# RiskChemi_Sensors_V2_04.net
KiCad netlist of a schematic drawn in Altium Designer
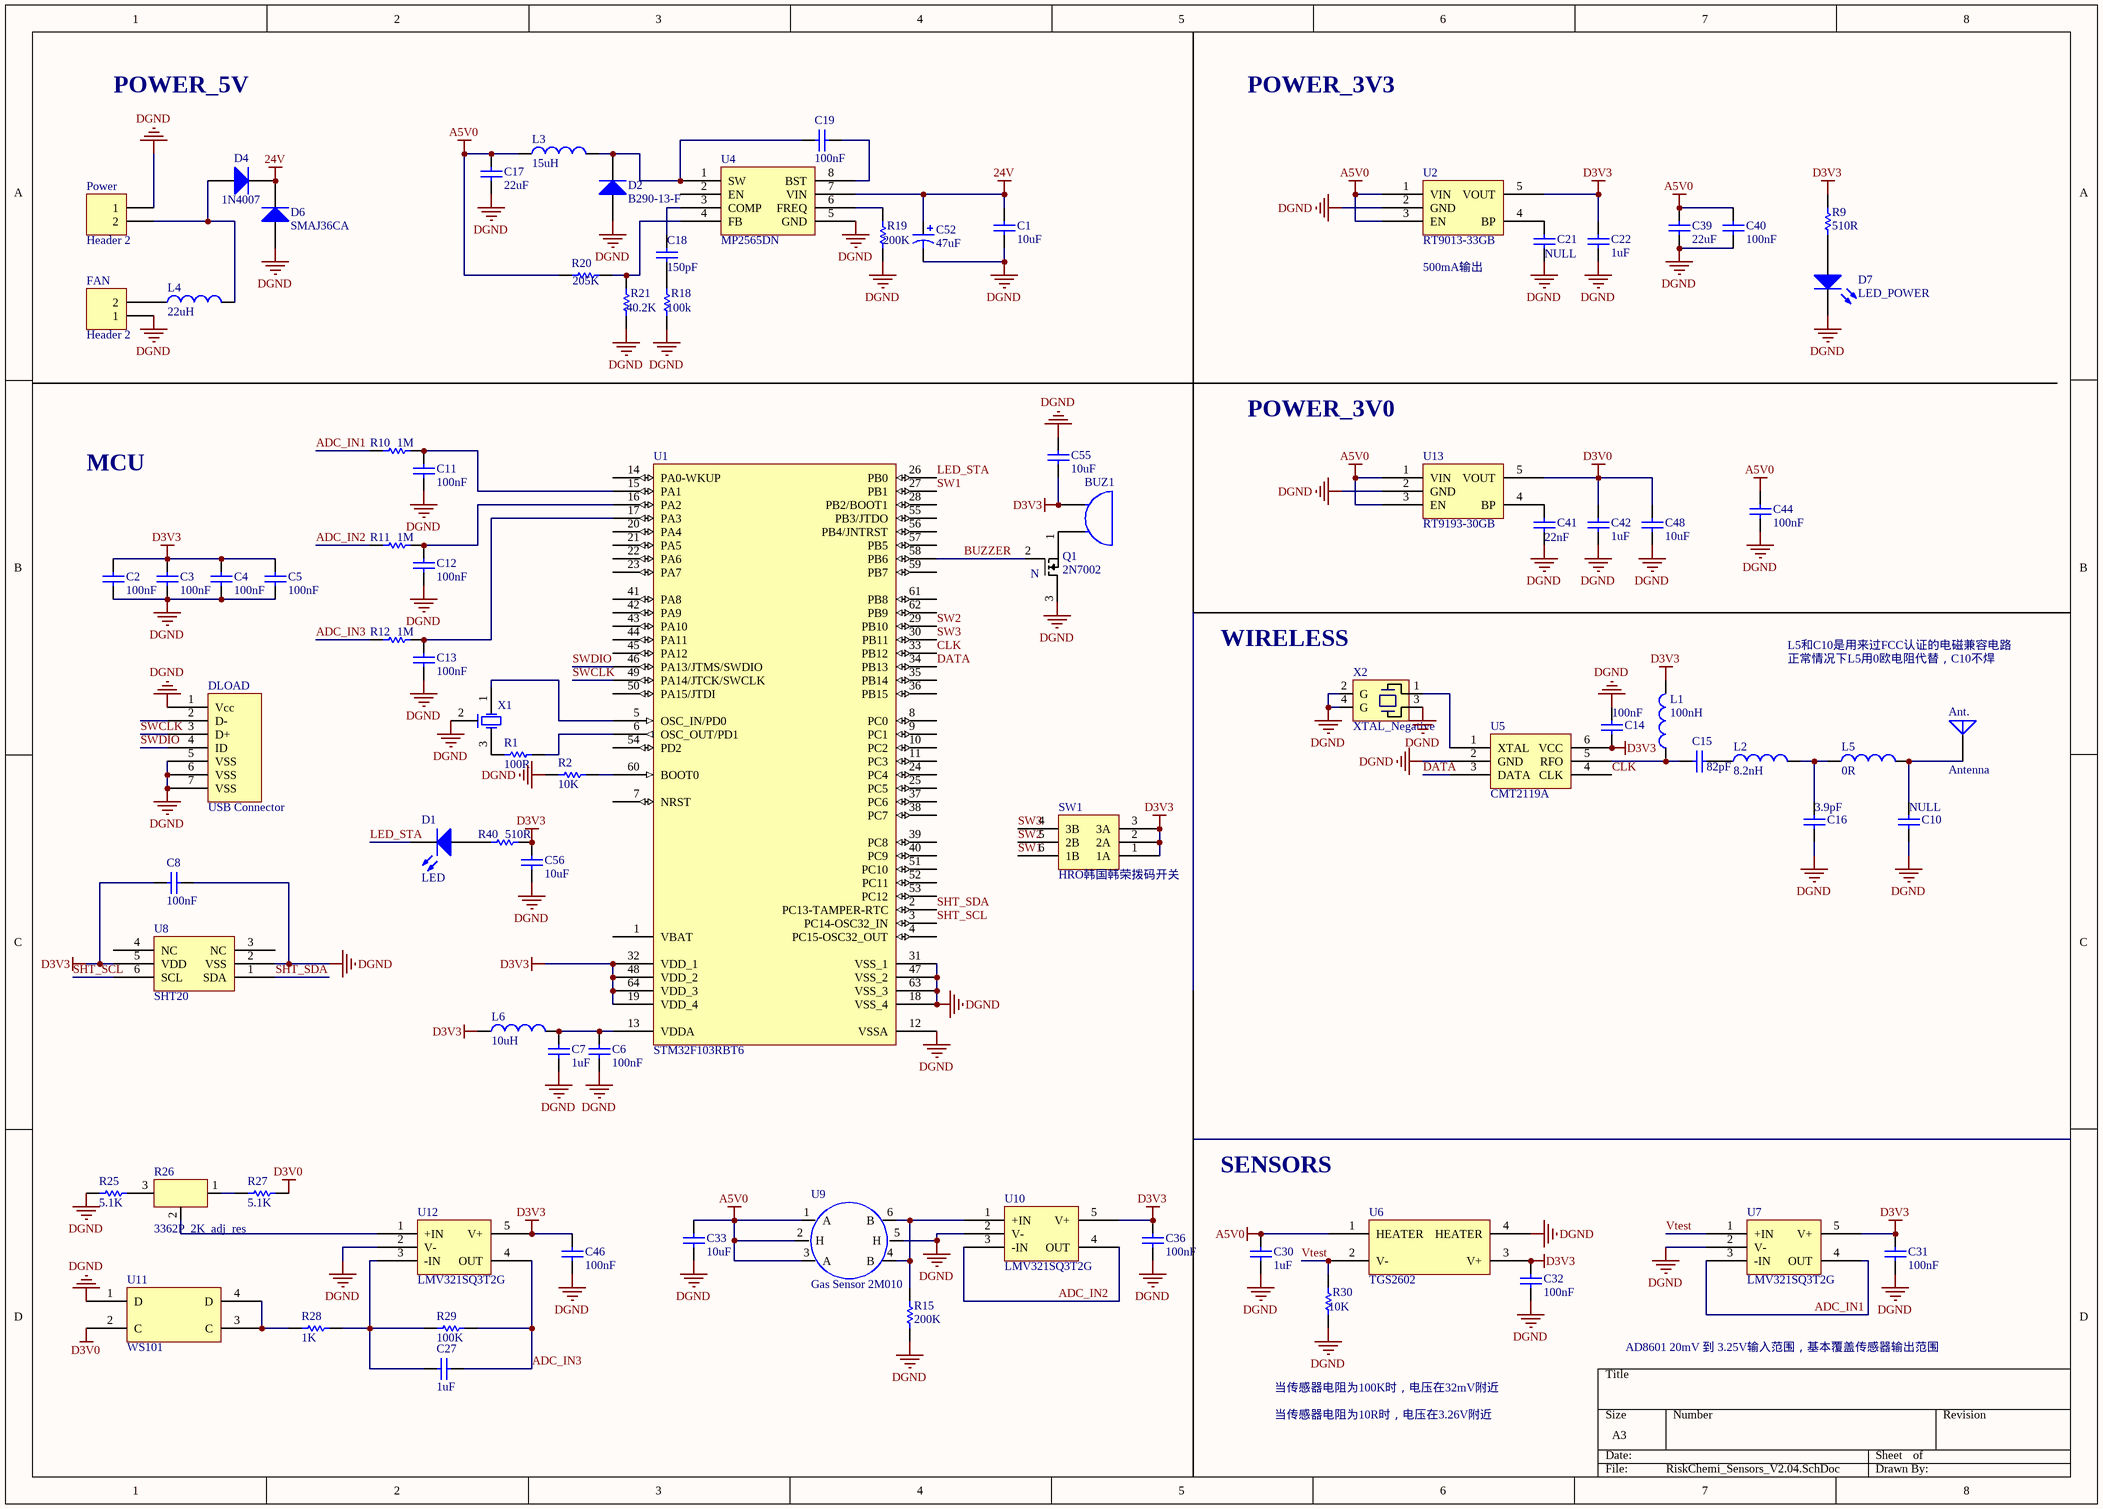
[diagram p0: RiskChemi_Sensors_V2.04.SchDoc]

(export (version "E")
  (design (tool "Eeschema 10.0.6"))
  (components
    (comp (ref "Ant.")
      (value "Antenna")
      (footprint "PIN1")
      (description "Generic Antenna")
      (fields (field (name "PUBLISHER") "Altium Limited"))
      (libsource (lib "Miscellaneous Devices") (part "Antenna"))
    )
    (comp (ref "BUZ1")
      (value "BUZZER 0905 through hole")
      (footprint "BUZ0905")
      (description "Buzzer")
      (libsource (lib "杂元件库") (part "BUZZER"))
    )
    (comp (ref "C1")
      (value "10uF")
      (footprint "0805")
      (description "Capacitor,50V")
      (fields (field (name "PUBLISHER") "Altium Limited"))
      (libsource (lib "Miscellaneous Devices") (part "Cap"))
    )
    (comp (ref "C2")
      (value "100nF")
      (footprint "BinFeng:0603")
      (description "Capacitor")
      (fields (field (name "PUBLISHER") "Altium Limited"))
      (libsource (lib "Miscellaneous Devices") (part "Cap"))
    )
    (comp (ref "C3")
      (value "100nF")
      (footprint "BinFeng:0603")
      (description "Capacitor")
      (fields (field (name "PUBLISHER") "Altium Limited"))
      (libsource (lib "Miscellaneous Devices") (part "Cap"))
    )
    (comp (ref "C4")
      (value "100nF")
      (footprint "BinFeng:0603")
      (description "Capacitor")
      (fields (field (name "PUBLISHER") "Altium Limited"))
      (libsource (lib "Miscellaneous Devices") (part "Cap"))
    )
    (comp (ref "C5")
      (value "100nF")
      (footprint "BinFeng:0603")
      (description "Capacitor")
      (fields (field (name "PUBLISHER") "Altium Limited"))
      (libsource (lib "Miscellaneous Devices") (part "Cap"))
    )
    (comp (ref "C6")
      (value "100nF")
      (footprint "BinFeng:0603")
      (description "Capacitor")
      (fields (field (name "PUBLISHER") "Altium Limited"))
      (libsource (lib "Miscellaneous Devices") (part "Cap"))
    )
    (comp (ref "C7")
      (value "1uF")
      (footprint "BinFeng:0603")
      (description "Capacitor")
      (fields (field (name "PUBLISHER") "Altium Limited"))
      (libsource (lib "Miscellaneous Devices") (part "Cap"))
    )
    (comp (ref "C8")
      (value "100nF")
      (footprint "BinFeng:0603")
      (description "Capacitor")
      (fields (field (name "PUBLISHER") "Altium Limited"))
      (libsource (lib "Miscellaneous Devices") (part "Cap"))
    )
    (comp (ref "C10")
      (value "NULL")
      (footprint "BinFeng:0402")
      (description "Capacitor")
      (fields (field (name "PUBLISHER") "Altium Limited"))
      (libsource (lib "Miscellaneous Devices") (part "Cap"))
    )
    (comp (ref "C11")
      (value "100nF")
      (footprint "BinFeng:0603")
      (description "Capacitor")
      (fields (field (name "PUBLISHER") "Altium Limited"))
      (libsource (lib "Miscellaneous Devices") (part "Cap"))
    )
    (comp (ref "C12")
      (value "100nF")
      (footprint "BinFeng:0603")
      (description "Capacitor")
      (fields (field (name "PUBLISHER") "Altium Limited"))
      (libsource (lib "Miscellaneous Devices") (part "Cap"))
    )
    (comp (ref "C13")
      (value "100nF")
      (footprint "BinFeng:0603")
      (description "Capacitor")
      (fields (field (name "PUBLISHER") "Altium Limited"))
      (libsource (lib "Miscellaneous Devices") (part "Cap"))
    )
    (comp (ref "C14")
      (value "100nF")
      (footprint "BinFeng:0402")
      (description "Capacitor")
      (fields (field (name "PUBLISHER") "Altium Limited"))
      (libsource (lib "Miscellaneous Devices") (part "Cap"))
    )
    (comp (ref "C15")
      (value "82pF")
      (footprint "BinFeng:0402")
      (description "Capacitor")
      (fields (field (name "PUBLISHER") "Altium Limited"))
      (libsource (lib "Miscellaneous Devices") (part "Cap"))
    )
    (comp (ref "C16")
      (value "3.9pF")
      (footprint "BinFeng:0402")
      (description "Capacitor")
      (fields (field (name "PUBLISHER") "Altium Limited"))
      (libsource (lib "Miscellaneous Devices") (part "Cap"))
    )
    (comp (ref "C17")
      (value "22uF")
      (footprint "0805")
      (description "Capacitor,50V")
      (fields (field (name "PUBLISHER") "Altium Limited"))
      (libsource (lib "Miscellaneous Devices") (part "Cap"))
    )
    (comp (ref "C18")
      (value "150pF")
      (footprint "BinFeng:0603")
      (description "Capacitor")
      (fields (field (name "PUBLISHER") "Altium Limited"))
      (libsource (lib "Miscellaneous Devices") (part "Cap"))
    )
    (comp (ref "C19")
      (value "100nF")
      (footprint "BinFeng:0603")
      (description "Capacitor")
      (fields (field (name "PUBLISHER") "Altium Limited"))
      (libsource (lib "Miscellaneous Devices") (part "Cap"))
    )
    (comp (ref "C21")
      (value "NULL")
      (footprint "BinFeng:0402")
      (description "Capacitor")
      (fields (field (name "PUBLISHER") "Altium Limited"))
      (libsource (lib "Miscellaneous Devices") (part "Cap"))
    )
    (comp (ref "C22")
      (value "1uF")
      (footprint "BinFeng:0402")
      (description "Capacitor")
      (fields (field (name "PUBLISHER") "Altium Limited"))
      (libsource (lib "Miscellaneous Devices") (part "Cap"))
    )
    (comp (ref "C27")
      (value "1uF")
      (footprint "BinFeng:0603")
      (description "Capacitor")
      (fields (field (name "PUBLISHER") "Altium Limited"))
      (libsource (lib "Miscellaneous Devices") (part "Cap"))
    )
    (comp (ref "C30")
      (value "1uF")
      (footprint "BinFeng:0603")
      (description "Capacitor")
      (fields (field (name "PUBLISHER") "Altium Limited"))
      (libsource (lib "Miscellaneous Devices") (part "Cap"))
    )
    (comp (ref "C31")
      (value "100nF")
      (footprint "BinFeng:0603")
      (description "Capacitor")
      (fields (field (name "PUBLISHER") "Altium Limited"))
      (libsource (lib "Miscellaneous Devices") (part "Cap"))
    )
    (comp (ref "C32")
      (value "100nF")
      (footprint "BinFeng:0603")
      (description "Capacitor")
      (fields (field (name "PUBLISHER") "Altium Limited"))
      (libsource (lib "Miscellaneous Devices") (part "Cap"))
    )
    (comp (ref "C33")
      (value "10uF")
      (footprint "0805")
      (description "Capacitor")
      (fields (field (name "PUBLISHER") "Altium Limited"))
      (libsource (lib "Miscellaneous Devices") (part "Cap"))
    )
    (comp (ref "C36")
      (value "100nF")
      (footprint "BinFeng:0603")
      (description "Capacitor")
      (fields (field (name "PUBLISHER") "Altium Limited"))
      (libsource (lib "Miscellaneous Devices") (part "Cap"))
    )
    (comp (ref "C39")
      (value "22uF")
      (footprint "1206")
      (description "Capacitor")
      (fields (field (name "PUBLISHER") "Altium Limited"))
      (libsource (lib "Miscellaneous Devices") (part "Cap"))
    )
    (comp (ref "C40")
      (value "100nF")
      (footprint "BinFeng:0402")
      (description "Capacitor")
      (fields (field (name "PUBLISHER") "Altium Limited"))
      (libsource (lib "Miscellaneous Devices") (part "Cap"))
    )
    (comp (ref "C41")
      (value "22nF")
      (footprint "BinFeng:0402")
      (description "Capacitor")
      (fields (field (name "PUBLISHER") "Altium Limited"))
      (libsource (lib "Miscellaneous Devices") (part "Cap"))
    )
    (comp (ref "C42")
      (value "1uF")
      (footprint "BinFeng:0402")
      (description "Capacitor")
      (fields (field (name "PUBLISHER") "Altium Limited"))
      (libsource (lib "Miscellaneous Devices") (part "Cap"))
    )
    (comp (ref "C44")
      (value "100nF")
      (footprint "BinFeng:0402")
      (description "Capacitor")
      (fields (field (name "PUBLISHER") "Altium Limited"))
      (libsource (lib "Miscellaneous Devices") (part "Cap"))
    )
    (comp (ref "C46")
      (value "100nF")
      (footprint "BinFeng:0603")
      (description "Capacitor")
      (fields (field (name "PUBLISHER") "Altium Limited"))
      (libsource (lib "Miscellaneous Devices") (part "Cap"))
    )
    (comp (ref "C48")
      (value "10uF")
      (footprint "0805")
      (description "Capacitor")
      (fields (field (name "PUBLISHER") "Altium Limited"))
      (libsource (lib "Miscellaneous Devices") (part "Cap"))
    )
    (comp (ref "C52")
      (value "47uF")
      (footprint "cap_pol_8*10.2")
      (description "Polarized Capacitor (Radial)")
      (fields (field (name "PUBLISHER") "Altium Limited"))
      (libsource (lib "Miscellaneous Devices") (part "Cap Pol1"))
    )
    (comp (ref "C55")
      (value "10uF")
      (footprint "0805")
      (description "Capacitor")
      (fields (field (name "PUBLISHER") "Altium Limited"))
      (libsource (lib "Miscellaneous Devices") (part "Cap"))
    )
    (comp (ref "C56")
      (value "10uF")
      (footprint "0805")
      (description "Capacitor")
      (fields (field (name "PUBLISHER") "Altium Limited"))
      (libsource (lib "Miscellaneous Devices") (part "Cap"))
    )
    (comp (ref "D1")
      (value "LED")
      (footprint "1206_LED")
      (description "Typical INFRARED GaAs LED")
      (fields (field (name "PUBLISHER") "Altium Limited"))
      (libsource (lib "Miscellaneous Devices") (part "LED0"))
    )
    (comp (ref "D2")
      (value "B290-13-F")
      (footprint "B290")
      (description "Default Diode")
      (fields (field (name "PUBLISHER") "Altium Limited"))
      (libsource (lib "Miscellaneous Devices") (part "Diode"))
    )
    (comp (ref "D4")
      (value "1N4007")
      (footprint "6032_pol")
      (description "1 Amp General Purpose Rectifier")
      (fields (field (name "PUBLISHER") "Altium Limited"))
      (libsource (lib "Miscellaneous Devices") (part "Diode 1N4007"))
    )
    (comp (ref "D6")
      (value "SMAJ36CA")
      (footprint "B290")
      (description "1 Amp General Purpose Rectifier")
      (fields (field (name "PUBLISHER") "Altium Limited"))
      (libsource (lib "Miscellaneous Devices") (part "Diode 1N4007"))
    )
    (comp (ref "D7")
      (value "LED_POWER")
      (footprint "1206_LED")
      (description "Typical INFRARED GaAs LED")
      (fields (field (name "PUBLISHER") "Altium Limited"))
      (libsource (lib "Miscellaneous Devices") (part "LED0"))
    )
    (comp (ref "DLOAD")
      (value "USB Connector")
      (footprint "Mini_USB")
      (libsource (lib "BinFeng_Connectors") (part "Component_1"))
    )
    (comp (ref "FAN")
      (value "Header 2")
      (footprint "HDR1X2")
      (description "Header, 2-Pin")
      (fields (field (name "PUBLISHER") "Altium Limited"))
      (libsource (lib "") (part "Header 2_1"))
    )
    (comp (ref "L1")
      (value "100nH")
      (footprint "0603C")
      (description "Inductor")
      (fields (field (name "PUBLISHER") "Altium Limited"))
      (libsource (lib "Miscellaneous Devices") (part "Inductor"))
    )
    (comp (ref "L2")
      (value "8.2nH")
      (footprint "0603C")
      (description "Inductor")
      (fields (field (name "PUBLISHER") "Altium Limited"))
      (libsource (lib "Miscellaneous Devices") (part "Inductor"))
    )
    (comp (ref "L3")
      (value "15uH")
      (footprint "4*4 Inductor")
      (description "Inductor, 1A")
      (fields (field (name "PUBLISHER") "Altium Limited"))
      (libsource (lib "Miscellaneous Devices") (part "Inductor"))
    )
    (comp (ref "L4")
      (value "22uH")
      (footprint "10*10Inductor")
      (description "Inductor, 1A")
      (fields (field (name "PUBLISHER") "Altium Limited"))
      (libsource (lib "Miscellaneous Devices") (part "Inductor"))
    )
    (comp (ref "L5")
      (value "0R")
      (footprint "0603C")
      (description "Inductor")
      (fields (field (name "PUBLISHER") "Altium Limited"))
      (libsource (lib "Miscellaneous Devices") (part "Inductor"))
    )
    (comp (ref "L6")
      (value "10uH")
      (footprint "0805")
      (description "Inductor")
      (fields (field (name "PUBLISHER") "Altium Limited"))
      (libsource (lib "Miscellaneous Devices") (part "Inductor"))
    )
    (comp (ref "Power")
      (value "Header 2")
      (footprint "HDR1X2")
      (description "Header, 2-Pin")
      (fields (field (name "PUBLISHER") "Altium Limited"))
      (libsource (lib "Miscellaneous Connectors") (part "Header 2"))
    )
    (comp (ref "Q1") (value "2N7002") (footprint "2N7002") (libsource (lib "seeder") (part "N-MOSFET")))
    (comp (ref "R1")
      (value "100R")
      (footprint "BinFeng:0603")
      (description "Resistor")
      (fields (field (name "PUBLISHER") "Altium Limited"))
      (libsource (lib "Miscellaneous Devices") (part "Res1"))
    )
    (comp (ref "R2")
      (value "10K")
      (footprint "BinFeng:0603")
      (description "Resistor")
      (fields (field (name "PUBLISHER") "Altium Limited"))
      (libsource (lib "Miscellaneous Devices") (part "Res1"))
    )
    (comp (ref "R9")
      (value "510R")
      (footprint "BinFeng:0603")
      (description "Resistor")
      (fields (field (name "PUBLISHER") "Altium Limited"))
      (libsource (lib "Miscellaneous Devices") (part "Res1"))
    )
    (comp (ref "R10")
      (value "1M")
      (footprint "BinFeng:0603")
      (description "Resistor")
      (fields (field (name "PUBLISHER") "Altium Limited"))
      (libsource (lib "Miscellaneous Devices") (part "Res1"))
    )
    (comp (ref "R11")
      (value "1M")
      (footprint "BinFeng:0603")
      (description "Resistor")
      (fields (field (name "PUBLISHER") "Altium Limited"))
      (libsource (lib "Miscellaneous Devices") (part "Res1"))
    )
    (comp (ref "R12")
      (value "1M")
      (footprint "BinFeng:0603")
      (description "Resistor")
      (fields (field (name "PUBLISHER") "Altium Limited"))
      (libsource (lib "Miscellaneous Devices") (part "Res1"))
    )
    (comp (ref "R15")
      (value "200K")
      (footprint "BinFeng:0603C")
      (description "Resistor")
      (fields (field (name "Comment") "Res1") (field (name "PUBLISHER") "Altium Limited"))
      (libsource (lib "Miscellaneous Devices") (part "Res1"))
    )
    (comp (ref "R18")
      (value "100k")
      (footprint "BinFeng:0603")
      (description "Resistor")
      (fields (field (name "PUBLISHER") "Altium Limited"))
      (libsource (lib "Miscellaneous Devices") (part "Res1"))
    )
    (comp (ref "R19")
      (value "200K")
      (footprint "BinFeng:0402")
      (description "Resistor")
      (fields (field (name "PUBLISHER") "Altium Limited"))
      (libsource (lib "Miscellaneous Devices") (part "Res1"))
    )
    (comp (ref "R20")
      (value "205K")
      (footprint "BinFeng:0603")
      (description "Resistor")
      (fields (field (name "PUBLISHER") "Altium Limited"))
      (libsource (lib "Miscellaneous Devices") (part "Res1"))
    )
    (comp (ref "R21")
      (value "40.2K")
      (footprint "BinFeng:0603")
      (description "Resistor")
      (fields (field (name "PUBLISHER") "Altium Limited"))
      (libsource (lib "Miscellaneous Devices") (part "Res1"))
    )
    (comp (ref "R25")
      (value "5.1K")
      (footprint "BinFeng:0603")
      (description "Resistor")
      (fields (field (name "PUBLISHER") "Altium Limited"))
      (libsource (lib "Miscellaneous Devices") (part "Res1"))
    )
    (comp (ref "R26")
      (value "3362P_2K_adj_res")
      (footprint "res_adj")
      (libsource (lib "BinFeng_IC") (part "res_adj"))
    )
    (comp (ref "R27")
      (value "5.1K")
      (footprint "BinFeng:0603")
      (description "Resistor")
      (fields (field (name "PUBLISHER") "Altium Limited"))
      (libsource (lib "Miscellaneous Devices") (part "Res1"))
    )
    (comp (ref "R28")
      (value "1K")
      (footprint "BinFeng:0603")
      (description "Resistor")
      (fields (field (name "PUBLISHER") "Altium Limited"))
      (libsource (lib "Miscellaneous Devices") (part "Res1"))
    )
    (comp (ref "R29")
      (value "100K")
      (footprint "BinFeng:0603")
      (description "Resistor")
      (fields (field (name "PUBLISHER") "Altium Limited"))
      (libsource (lib "Miscellaneous Devices") (part "Res1"))
    )
    (comp (ref "R30")
      (value "10K")
      (footprint "BinFeng:0603")
      (description "Resistor")
      (fields (field (name "PUBLISHER") "Altium Limited"))
      (libsource (lib "Miscellaneous Devices") (part "Res1"))
    )
    (comp (ref "R40")
      (value "510R")
      (footprint "BinFeng:0603")
      (description "Resistor")
      (fields (field (name "PUBLISHER") "Altium Limited"))
      (libsource (lib "Miscellaneous Devices") (part "Res1"))
    )
    (comp (ref "SW1")
      (value "HRO韩国韩荣拨码开关")
      (footprint "SW_6P_HRO")
      (libsource (lib "BinFeng_IC") (part "SW_6P"))
    )
    (comp (ref "U1")
      (value "STM32F103RBT6")
      (footprint "LQFP64_N")
      (description "STM32 ARM-based 32-bit MCU with 64 Kbytes Flash, 64-pin LQFP, Industrial Temperature")
      (fields (field (name "PUBLISHER") "Altium Limited"))
      (libsource (lib "ST Microcontroller 32-Bit STM32") (part "STM32F103R8T6"))
    )
    (comp (ref "U2")
      (value "RT9013-33GB")
      (footprint "SOT-23-5")
      (libsource (lib "BinFeng_IC") (part "RT9193"))
    )
    (comp (ref "U4")
      (value "MP2565DN")
      (footprint "so-8")
      (description "DCDC 4.5V~28V input 1.8V ~5V output low power")
      (libsource (lib "BinFeng_IC") (part "MP1584"))
    )
    (comp (ref "U5")
      (value "CMT2119A")
      (footprint "sot23-6")
      (libsource (lib "BinFeng_IC") (part "CMT2119A"))
    )
    (comp (ref "U6")
      (value "TGS2602")
      (footprint "Gas Sensor TGS2602 Slot")
      (description "VOC sensor")
      (libsource (lib "BinFeng_IC") (part "TGS2602"))
    )
    (comp (ref "U7")
      (value "LMV321SQ3T2G")
      (footprint "SC-70-5")
      (libsource (lib "BinFeng_IC") (part "LMV321SQ3T2G"))
    )
    (comp (ref "U8") (value "SHT20") (footprint "SHT20") (libsource (lib "BinFeng_IC") (part "SHT20")))
    (comp (ref "U9")
      (value "Gas Sensor 2M010")
      (footprint "Gas Sensor 2M010 Slot")
      (libsource (lib "BinFeng_IC") (part "Gas Sensor"))
    )
    (comp (ref "U10")
      (value "LMV321SQ3T2G")
      (footprint "SC-70-5")
      (libsource (lib "BinFeng_IC") (part "LMV321SQ3T2G"))
    )
    (comp (ref "U11")
      (value "WS101")
      (footprint "Gas_Sensor_WS101_Slot")
      (libsource (lib "BinFeng_IC") (part "Gas Sensor_WS101"))
    )
    (comp (ref "U12")
      (value "LMV321SQ3T2G")
      (footprint "SC-70-5")
      (libsource (lib "BinFeng_IC") (part "LMV321SQ3T2G"))
    )
    (comp (ref "U13")
      (value "RT9193-30GB")
      (footprint "SOT-23-5")
      (libsource (lib "BinFeng_IC") (part "RT9193"))
    )
    (comp (ref "X1") (value "8M smd") (footprint "8Mhz_XTAL") (libsource (lib "Schlib1") (part "8M smd")))
    (comp (ref "X2")
      (value "XTAL_Negative")
      (footprint "XTAL3225")
      (libsource (lib "BinFeng_IC") (part "XTAL_Negative"))
    )
  )
  (nets
    (net (code "1") (name "/ADC_IN1") (class "Default")
      (node (ref "R10") (pin "1") (pinfunction "1_1") (pintype "passive"))
      (node (ref "U7") (pin "3") (pinfunction "-IN_3") (pintype "passive"))
      (node (ref "U7") (pin "4") (pinfunction "OUT_4") (pintype "passive"))
    )
    (net (code "2") (name "/ADC_IN2") (class "Default")
      (node (ref "R11") (pin "1") (pinfunction "1_1") (pintype "passive"))
      (node (ref "U10") (pin "3") (pinfunction "-IN_3") (pintype "passive"))
      (node (ref "U10") (pin "4") (pinfunction "OUT_4") (pintype "passive"))
    )
    (net (code "3") (name "/ADC_IN3") (class "Default")
      (node (ref "C27") (pin "1") (pinfunction "1_1") (pintype "passive"))
      (node (ref "R12") (pin "1") (pinfunction "1_1") (pintype "passive"))
      (node (ref "R29") (pin "2") (pinfunction "2_2") (pintype "passive"))
      (node (ref "U12") (pin "4") (pinfunction "OUT_4") (pintype "passive"))
    )
    (net (code "4") (name "/BUZZER") (class "Default")
      (node (ref "Q1") (pin "2") (pinfunction "G_2") (pintype "passive"))
      (node (ref "U1") (pin "58") (pinfunction "PB6_58") (pintype "bidirectional"))
    )
    (net (code "5") (name "/CLK") (class "Default")
      (node (ref "U1") (pin "33") (pinfunction "PB12_33") (pintype "bidirectional"))
      (node (ref "U5") (pin "4") (pinfunction "CLK_4") (pintype "passive"))
    )
    (net (code "6") (name "/DATA") (class "Default")
      (node (ref "U1") (pin "34") (pinfunction "PB13_34") (pintype "bidirectional"))
      (node (ref "U5") (pin "3") (pinfunction "DATA_3") (pintype "passive"))
    )
    (net (code "7") (name "/LED_STA") (class "Default")
      (node (ref "D1") (pin "2") (pinfunction "K_2") (pintype "passive"))
      (node (ref "U1") (pin "26") (pinfunction "PB0_26") (pintype "bidirectional"))
    )
    (net (code "8") (name "/SHT_SCL") (class "Default")
      (node (ref "U1") (pin "3") (pinfunction "PC14-OSC32_IN_3") (pintype "bidirectional"))
      (node (ref "U8") (pin "6") (pinfunction "SCL_6") (pintype "passive"))
    )
    (net (code "9") (name "/SHT_SDA") (class "Default")
      (node (ref "U1") (pin "2") (pinfunction "PC13-TAMPER-RTC_2") (pintype "bidirectional"))
      (node (ref "U8") (pin "1") (pinfunction "SDA_1") (pintype "passive"))
    )
    (net (code "10") (name "/SW1") (class "Default")
      (node (ref "SW1") (pin "6") (pinfunction "1B_6") (pintype "passive"))
      (node (ref "U1") (pin "27") (pinfunction "PB1_27") (pintype "bidirectional"))
    )
    (net (code "11") (name "/SW2") (class "Default")
      (node (ref "SW1") (pin "5") (pinfunction "2B_5") (pintype "passive"))
      (node (ref "U1") (pin "29") (pinfunction "PB10_29") (pintype "bidirectional"))
    )
    (net (code "12") (name "/SW3") (class "Default")
      (node (ref "SW1") (pin "4") (pinfunction "3B_4") (pintype "passive"))
      (node (ref "U1") (pin "30") (pinfunction "PB11_30") (pintype "bidirectional"))
    )
    (net (code "13") (name "/SWCLK") (class "Default")
      (node (ref "DLOAD") (pin "3") (pinfunction "D+_3") (pintype "passive"))
      (node (ref "U1") (pin "49") (pinfunction "PA14/JTCK/SWCLK_49") (pintype "bidirectional"))
    )
    (net (code "14") (name "/SWDIO") (class "Default")
      (node (ref "DLOAD") (pin "4") (pinfunction "ID_4") (pintype "passive"))
      (node (ref "U1") (pin "46") (pinfunction "PA13/JTMS/SWDIO_46") (pintype "bidirectional"))
    )
    (net (code "15") (name "/Vtest") (class "Default")
      (node (ref "R30") (pin "2") (pinfunction "2_2") (pintype "passive"))
      (node (ref "U6") (pin "2") (pinfunction "V-_2") (pintype "passive"))
      (node (ref "U7") (pin "1") (pinfunction "+IN_1") (pintype "passive"))
    )
    (net (code "16") (name "24V") (class "Default")
      (node (ref "C1") (pin "2") (pinfunction "2_2") (pintype "passive"))
      (node (ref "C52") (pin "1") (pinfunction "1_1") (pintype "passive"))
      (node (ref "D4") (pin "2") (pinfunction "K_2") (pintype "passive"))
      (node (ref "D6") (pin "2") (pinfunction "K_2") (pintype "passive"))
      (node (ref "U4") (pin "7") (pinfunction "VIN_7") (pintype "passive"))
    )
    (net (code "17") (name "A5V0") (class "Default")
      (node (ref "C17") (pin "2") (pinfunction "2_2") (pintype "passive"))
      (node (ref "C30") (pin "2") (pinfunction "2_2") (pintype "passive"))
      (node (ref "C33") (pin "2") (pinfunction "2_2") (pintype "passive"))
      (node (ref "C39") (pin "1") (pinfunction "1_1") (pintype "passive"))
      (node (ref "C40") (pin "2") (pinfunction "2_2") (pintype "passive"))
      (node (ref "C44") (pin "2") (pinfunction "2_2") (pintype "passive"))
      (node (ref "L3") (pin "1") (pinfunction "1_1") (pintype "passive"))
      (node (ref "R20") (pin "2") (pinfunction "2_2") (pintype "passive"))
      (node (ref "U13") (pin "1") (pinfunction "VIN_1") (pintype "passive"))
      (node (ref "U13") (pin "3") (pinfunction "EN_3") (pintype "passive"))
      (node (ref "U2") (pin "1") (pinfunction "VIN_1") (pintype "passive"))
      (node (ref "U2") (pin "3") (pinfunction "EN_3") (pintype "passive"))
      (node (ref "U6") (pin "1") (pinfunction "HEATER_1") (pintype "passive"))
      (node (ref "U9") (pin "1") (pinfunction "A_1") (pintype "passive"))
      (node (ref "U9") (pin "2") (pinfunction "H_2") (pintype "passive"))
      (node (ref "U9") (pin "3") (pinfunction "A_3") (pintype "passive"))
    )
    (net (code "18") (name "D3V0") (class "Default")
      (node (ref "C42") (pin "2") (pinfunction "2_2") (pintype "passive"))
      (node (ref "C48") (pin "2") (pinfunction "2_2") (pintype "passive"))
      (node (ref "R27") (pin "2") (pinfunction "2_2") (pintype "passive"))
      (node (ref "U11") (pin "2") (pinfunction "C_2") (pintype "passive"))
      (node (ref "U13") (pin "5") (pinfunction "VOUT_5") (pintype "passive"))
    )
    (net (code "19") (name "D3V3") (class "Default")
      (node (ref "BUZ1") (pin "1") (pinfunction "A_1") (pintype "passive"))
      (node (ref "C14") (pin "2") (pinfunction "2_2") (pintype "passive"))
      (node (ref "C2") (pin "2") (pinfunction "2_2") (pintype "passive"))
      (node (ref "C22") (pin "2") (pinfunction "2_2") (pintype "passive"))
      (node (ref "C3") (pin "2") (pinfunction "2_2") (pintype "passive"))
      (node (ref "C31") (pin "2") (pinfunction "2_2") (pintype "passive"))
      (node (ref "C32") (pin "2") (pinfunction "2_2") (pintype "passive"))
      (node (ref "C36") (pin "2") (pinfunction "2_2") (pintype "passive"))
      (node (ref "C4") (pin "2") (pinfunction "2_2") (pintype "passive"))
      (node (ref "C46") (pin "2") (pinfunction "2_2") (pintype "passive"))
      (node (ref "C5") (pin "2") (pinfunction "2_2") (pintype "passive"))
      (node (ref "C55") (pin "2") (pinfunction "2_2") (pintype "passive"))
      (node (ref "C56") (pin "2") (pinfunction "2_2") (pintype "passive"))
      (node (ref "C8") (pin "2") (pinfunction "2_2") (pintype "passive"))
      (node (ref "L1") (pin "2") (pinfunction "2_2") (pintype "passive"))
      (node (ref "L6") (pin "1") (pinfunction "1_1") (pintype "passive"))
      (node (ref "R40") (pin "2") (pinfunction "2_2") (pintype "passive"))
      (node (ref "R9") (pin "2") (pinfunction "2_2") (pintype "passive"))
      (node (ref "SW1") (pin "1") (pinfunction "1A_1") (pintype "passive"))
      (node (ref "SW1") (pin "2") (pinfunction "2A_2") (pintype "passive"))
      (node (ref "SW1") (pin "3") (pinfunction "3A_3") (pintype "passive"))
      (node (ref "U1") (pin "19") (pinfunction "VDD_4_19") (pintype "power_in"))
      (node (ref "U1") (pin "32") (pinfunction "VDD_1_32") (pintype "power_in"))
      (node (ref "U1") (pin "48") (pinfunction "VDD_2_48") (pintype "power_in"))
      (node (ref "U1") (pin "64") (pinfunction "VDD_3_64") (pintype "power_in"))
      (node (ref "U10") (pin "5") (pinfunction "V+_5") (pintype "passive"))
      (node (ref "U12") (pin "5") (pinfunction "V+_5") (pintype "passive"))
      (node (ref "U2") (pin "5") (pinfunction "VOUT_5") (pintype "passive"))
      (node (ref "U5") (pin "6") (pinfunction "VCC_6") (pintype "passive"))
      (node (ref "U6") (pin "3") (pinfunction "V+_3") (pintype "passive"))
      (node (ref "U7") (pin "5") (pinfunction "V+_5") (pintype "passive"))
      (node (ref "U8") (pin "5") (pinfunction "VDD_5") (pintype "passive"))
    )
    (net (code "20") (name "DGND") (class "Default")
      (node (ref "C1") (pin "1") (pinfunction "1_1") (pintype "passive"))
      (node (ref "C10") (pin "1") (pinfunction "1_1") (pintype "passive"))
      (node (ref "C11") (pin "2") (pinfunction "2_2") (pintype "passive"))
      (node (ref "C12") (pin "1") (pinfunction "1_1") (pintype "passive"))
      (node (ref "C13") (pin "1") (pinfunction "1_1") (pintype "passive"))
      (node (ref "C14") (pin "1") (pinfunction "1_1") (pintype "passive"))
      (node (ref "C16") (pin "1") (pinfunction "1_1") (pintype "passive"))
      (node (ref "C17") (pin "1") (pinfunction "1_1") (pintype "passive"))
      (node (ref "C2") (pin "1") (pinfunction "1_1") (pintype "passive"))
      (node (ref "C21") (pin "1") (pinfunction "1_1") (pintype "passive"))
      (node (ref "C22") (pin "1") (pinfunction "1_1") (pintype "passive"))
      (node (ref "C3") (pin "1") (pinfunction "1_1") (pintype "passive"))
      (node (ref "C30") (pin "1") (pinfunction "1_1") (pintype "passive"))
      (node (ref "C31") (pin "1") (pinfunction "1_1") (pintype "passive"))
      (node (ref "C32") (pin "1") (pinfunction "1_1") (pintype "passive"))
      (node (ref "C33") (pin "1") (pinfunction "1_1") (pintype "passive"))
      (node (ref "C36") (pin "1") (pinfunction "1_1") (pintype "passive"))
      (node (ref "C39") (pin "2") (pinfunction "2_2") (pintype "passive"))
      (node (ref "C4") (pin "1") (pinfunction "1_1") (pintype "passive"))
      (node (ref "C40") (pin "1") (pinfunction "1_1") (pintype "passive"))
      (node (ref "C41") (pin "1") (pinfunction "1_1") (pintype "passive"))
      (node (ref "C42") (pin "1") (pinfunction "1_1") (pintype "passive"))
      (node (ref "C44") (pin "1") (pinfunction "1_1") (pintype "passive"))
      (node (ref "C46") (pin "1") (pinfunction "1_1") (pintype "passive"))
      (node (ref "C48") (pin "1") (pinfunction "1_1") (pintype "passive"))
      (node (ref "C5") (pin "1") (pinfunction "1_1") (pintype "passive"))
      (node (ref "C52") (pin "2") (pinfunction "2_2") (pintype "passive"))
      (node (ref "C55") (pin "1") (pinfunction "1_1") (pintype "passive"))
      (node (ref "C56") (pin "1") (pinfunction "1_1") (pintype "passive"))
      (node (ref "C6") (pin "1") (pinfunction "1_1") (pintype "passive"))
      (node (ref "C7") (pin "1") (pinfunction "1_1") (pintype "passive"))
      (node (ref "C8") (pin "1") (pinfunction "1_1") (pintype "passive"))
      (node (ref "D2") (pin "1") (pinfunction "A_1") (pintype "passive"))
      (node (ref "D6") (pin "1") (pinfunction "A_1") (pintype "passive"))
      (node (ref "D7") (pin "2") (pinfunction "K_2") (pintype "passive"))
      (node (ref "DLOAD") (pin "1") (pinfunction "Vcc_1") (pintype "passive"))
      (node (ref "DLOAD") (pin "5") (pinfunction "VSS_5") (pintype "passive"))
      (node (ref "DLOAD") (pin "6") (pinfunction "VSS_6") (pintype "passive"))
      (node (ref "DLOAD") (pin "7") (pinfunction "VSS_7") (pintype "passive"))
      (node (ref "FAN") (pin "1") (pinfunction "1_1") (pintype "passive"))
      (node (ref "Power") (pin "1") (pinfunction "1_1") (pintype "passive"))
      (node (ref "Q1") (pin "3") (pinfunction "S_3") (pintype "passive"))
      (node (ref "R15") (pin "2") (pinfunction "2_2") (pintype "passive"))
      (node (ref "R18") (pin "1") (pinfunction "1_1") (pintype "passive"))
      (node (ref "R19") (pin "1") (pinfunction "1_1") (pintype "passive"))
      (node (ref "R2") (pin "1") (pinfunction "1_1") (pintype "passive"))
      (node (ref "R21") (pin "1") (pinfunction "1_1") (pintype "passive"))
      (node (ref "R25") (pin "1") (pinfunction "1_1") (pintype "passive"))
      (node (ref "R30") (pin "1") (pinfunction "1_1") (pintype "passive"))
      (node (ref "U1") (pin "12") (pinfunction "VSSA_12") (pintype "power_in"))
      (node (ref "U1") (pin "18") (pinfunction "VSS_4_18") (pintype "power_in"))
      (node (ref "U1") (pin "31") (pinfunction "VSS_1_31") (pintype "power_in"))
      (node (ref "U1") (pin "47") (pinfunction "VSS_2_47") (pintype "power_in"))
      (node (ref "U1") (pin "63") (pinfunction "VSS_3_63") (pintype "power_in"))
      (node (ref "U10") (pin "2") (pinfunction "V-_2") (pintype "passive"))
      (node (ref "U11") (pin "1") (pinfunction "D_1") (pintype "passive"))
      (node (ref "U12") (pin "2") (pinfunction "V-_2") (pintype "passive"))
      (node (ref "U13") (pin "2") (pinfunction "GND_2") (pintype "passive"))
      (node (ref "U2") (pin "2") (pinfunction "GND_2") (pintype "passive"))
      (node (ref "U4") (pin "5") (pinfunction "GND_5") (pintype "passive"))
      (node (ref "U5") (pin "2") (pinfunction "GND_2") (pintype "passive"))
      (node (ref "U6") (pin "4") (pinfunction "HEATER_4") (pintype "passive"))
      (node (ref "U7") (pin "2") (pinfunction "V-_2") (pintype "passive"))
      (node (ref "U8") (pin "2") (pinfunction "VSS_2") (pintype "passive"))
      (node (ref "U9") (pin "5") (pinfunction "H_5") (pintype "passive"))
      (node (ref "X1") (pin "2") (pinfunction "GND_2") (pintype "passive"))
      (node (ref "X2") (pin "2") (pinfunction "G_2") (pintype "passive"))
      (node (ref "X2") (pin "3") (pintype "passive"))
      (node (ref "X2") (pin "4") (pinfunction "G_4") (pintype "passive"))
    )
    (net (code "21") (name "Net-(Ant.-A)") (class "Default")
      (node (ref "Ant.") (pin "1") (pinfunction "A_1") (pintype "passive"))
      (node (ref "C10") (pin "2") (pinfunction "2_2") (pintype "passive"))
      (node (ref "L5") (pin "2") (pinfunction "2_2") (pintype "passive"))
    )
    (net (code "22") (name "Net-(BUZ1-B)") (class "Default")
      (node (ref "BUZ1") (pin "2") (pinfunction "B_2") (pintype "passive"))
      (node (ref "Q1") (pin "1") (pinfunction "D_1") (pintype "passive"))
    )
    (net (code "23") (name "Net-(C15-Pad2)") (class "Default")
      (node (ref "C15") (pin "2") (pinfunction "2_2") (pintype "passive"))
      (node (ref "L2") (pin "1") (pinfunction "1_1") (pintype "passive"))
    )
    (net (code "24") (name "Net-(C16-Pad2)") (class "Default")
      (node (ref "C16") (pin "2") (pinfunction "2_2") (pintype "passive"))
      (node (ref "L2") (pin "2") (pinfunction "2_2") (pintype "passive"))
      (node (ref "L5") (pin "1") (pinfunction "1_1") (pintype "passive"))
    )
    (net (code "25") (name "Net-(C18-Pad2)") (class "Default")
      (node (ref "C18") (pin "2") (pinfunction "2_2") (pintype "passive"))
      (node (ref "R18") (pin "2") (pinfunction "2_2") (pintype "passive"))
    )
    (net (code "26") (name "Net-(D1-A)") (class "Default")
      (node (ref "D1") (pin "1") (pinfunction "A_1") (pintype "passive"))
      (node (ref "R40") (pin "1") (pinfunction "1_1") (pintype "passive"))
    )
    (net (code "27") (name "Net-(D2-K)") (class "Default")
      (node (ref "C19") (pin "2") (pinfunction "2_2") (pintype "passive"))
      (node (ref "D2") (pin "2") (pinfunction "K_2") (pintype "passive"))
      (node (ref "L3") (pin "2") (pinfunction "2_2") (pintype "passive"))
      (node (ref "U4") (pin "1") (pinfunction "SW_1") (pintype "passive"))
    )
    (net (code "28") (name "Net-(D4-A)") (class "Default")
      (node (ref "D4") (pin "1") (pinfunction "A_1") (pintype "passive"))
      (node (ref "L4") (pin "2") (pinfunction "2_2") (pintype "passive"))
      (node (ref "Power") (pin "2") (pinfunction "2_2") (pintype "passive"))
    )
    (net (code "29") (name "Net-(D7-A)") (class "Default")
      (node (ref "D7") (pin "1") (pinfunction "A_1") (pintype "passive"))
      (node (ref "R9") (pin "1") (pinfunction "1_1") (pintype "passive"))
    )
    (net (code "30") (name "Net-(FAN-Pad2)") (class "Default")
      (node (ref "FAN") (pin "2") (pinfunction "2_2") (pintype "passive"))
      (node (ref "L4") (pin "1") (pinfunction "1_1") (pintype "passive"))
    )
    (net (code "31") (name "Net-(R25-Pad2)") (class "Default")
      (node (ref "R25") (pin "2") (pinfunction "2_2") (pintype "passive"))
      (node (ref "R26") (pin "3") (pintype "passive"))
    )
    (net (code "32") (name "Net-(R26-Pad1)") (class "Default")
      (node (ref "R26") (pin "1") (pintype "passive"))
      (node (ref "R27") (pin "1") (pinfunction "1_1") (pintype "passive"))
    )
    (net (code "33") (name "Net-(R28-Pad1)") (class "Default")
      (node (ref "R28") (pin "1") (pinfunction "1_1") (pintype "passive"))
      (node (ref "U11") (pin "3") (pinfunction "C_3") (pintype "passive"))
      (node (ref "U11") (pin "4") (pinfunction "D_4") (pintype "passive"))
    )
    (net (code "34") (name "Net-(U1-BOOT0)") (class "Default")
      (node (ref "R2") (pin "2") (pinfunction "2_2") (pintype "passive"))
      (node (ref "U1") (pin "60") (pinfunction "BOOT0_60") (pintype "input"))
    )
    (net (code "35") (name "Net-(U1-OSC_IN{slash}PD0)") (class "Default")
      (node (ref "U1") (pin "5") (pinfunction "OSC_IN/PD0_5") (pintype "input"))
      (node (ref "X1") (pin "1") (pinfunction "OSC1_1") (pintype "passive"))
    )
    (net (code "36") (name "Net-(U1-OSC_OUT{slash}PD1)") (class "Default")
      (node (ref "R1") (pin "2") (pinfunction "2_2") (pintype "passive"))
      (node (ref "U1") (pin "6") (pinfunction "OSC_OUT/PD1_6") (pintype "output"))
    )
    (net (code "37") (name "Net-(U1-PA1)") (class "Default")
      (node (ref "C11") (pin "1") (pinfunction "1_1") (pintype "passive"))
      (node (ref "R10") (pin "2") (pinfunction "2_2") (pintype "passive"))
      (node (ref "U1") (pin "15") (pinfunction "PA1_15") (pintype "bidirectional"))
    )
    (net (code "38") (name "Net-(U1-PA2)") (class "Default")
      (node (ref "C12") (pin "2") (pinfunction "2_2") (pintype "passive"))
      (node (ref "R11") (pin "2") (pinfunction "2_2") (pintype "passive"))
      (node (ref "U1") (pin "16") (pinfunction "PA2_16") (pintype "bidirectional"))
    )
    (net (code "39") (name "Net-(U1-PA3)") (class "Default")
      (node (ref "C13") (pin "2") (pinfunction "2_2") (pintype "passive"))
      (node (ref "R12") (pin "2") (pinfunction "2_2") (pintype "passive"))
      (node (ref "U1") (pin "17") (pinfunction "PA3_17") (pintype "bidirectional"))
    )
    (net (code "40") (name "Net-(U1-VDDA)") (class "Default")
      (node (ref "C6") (pin "2") (pinfunction "2_2") (pintype "passive"))
      (node (ref "C7") (pin "2") (pinfunction "2_2") (pintype "passive"))
      (node (ref "L6") (pin "2") (pinfunction "2_2") (pintype "passive"))
      (node (ref "U1") (pin "13") (pinfunction "VDDA_13") (pintype "power_in"))
    )
    (net (code "41") (name "Net-(U2-BP)") (class "Default")
      (node (ref "C21") (pin "2") (pinfunction "2_2") (pintype "passive"))
      (node (ref "U2") (pin "4") (pinfunction "BP_4") (pintype "passive"))
    )
    (net (code "42") (name "Net-(U4-BST)") (class "Default")
      (node (ref "C19") (pin "1") (pinfunction "1_1") (pintype "passive"))
      (node (ref "U4") (pin "8") (pinfunction "BST_8") (pintype "passive"))
    )
    (net (code "43") (name "Net-(U4-COMP)") (class "Default")
      (node (ref "C18") (pin "1") (pinfunction "1_1") (pintype "passive"))
      (node (ref "U4") (pin "3") (pinfunction "COMP_3") (pintype "passive"))
    )
    (net (code "44") (name "Net-(U4-FB)") (class "Default")
      (node (ref "R20") (pin "1") (pinfunction "1_1") (pintype "passive"))
      (node (ref "R21") (pin "2") (pinfunction "2_2") (pintype "passive"))
      (node (ref "U4") (pin "4") (pinfunction "FB_4") (pintype "passive"))
    )
    (net (code "45") (name "Net-(U4-FREQ)") (class "Default")
      (node (ref "R19") (pin "2") (pinfunction "2_2") (pintype "passive"))
      (node (ref "U4") (pin "6") (pinfunction "FREQ_6") (pintype "passive"))
    )
    (net (code "46") (name "Net-(U5-RFO)") (class "Default")
      (node (ref "C15") (pin "1") (pinfunction "1_1") (pintype "passive"))
      (node (ref "L1") (pin "1") (pinfunction "1_1") (pintype "passive"))
      (node (ref "U5") (pin "5") (pinfunction "RFO_5") (pintype "passive"))
    )
    (net (code "47") (name "Net-(U5-XTAL)") (class "Default")
      (node (ref "U5") (pin "1") (pinfunction "XTAL_1") (pintype "passive"))
      (node (ref "X2") (pin "1") (pintype "passive"))
    )
    (net (code "48") (name "Net-(U10-+IN)") (class "Default")
      (node (ref "R15") (pin "1") (pinfunction "1_1") (pintype "passive"))
      (node (ref "U10") (pin "1") (pinfunction "+IN_1") (pintype "passive"))
      (node (ref "U9") (pin "4") (pinfunction "B_4") (pintype "passive"))
      (node (ref "U9") (pin "6") (pinfunction "B_6") (pintype "passive"))
    )
    (net (code "49") (name "Net-(U12-+IN)") (class "Default")
      (node (ref "R26") (pin "2") (pintype "passive"))
      (node (ref "U12") (pin "1") (pinfunction "+IN_1") (pintype "passive"))
    )
    (net (code "50") (name "Net-(U12--IN)") (class "Default")
      (node (ref "C27") (pin "2") (pinfunction "2_2") (pintype "passive"))
      (node (ref "R28") (pin "2") (pinfunction "2_2") (pintype "passive"))
      (node (ref "R29") (pin "1") (pinfunction "1_1") (pintype "passive"))
      (node (ref "U12") (pin "3") (pinfunction "-IN_3") (pintype "passive"))
    )
    (net (code "51") (name "Net-(U13-BP)") (class "Default")
      (node (ref "C41") (pin "2") (pinfunction "2_2") (pintype "passive"))
      (node (ref "U13") (pin "4") (pinfunction "BP_4") (pintype "passive"))
    )
    (net (code "52") (name "Net-(X1-OSC2)") (class "Default")
      (node (ref "R1") (pin "1") (pinfunction "1_1") (pintype "passive"))
      (node (ref "X1") (pin "3") (pinfunction "OSC2_3") (pintype "passive"))
    )
    (net (code "53") (name "unconnected-(DLOAD-D--Pad2)") (class "Default")
      (node (ref "DLOAD") (pin "2") (pinfunction "D-_2") (pintype "passive"))
    )
    (net (code "54") (name "unconnected-(U1-NRST-Pad7)") (class "Default")
      (node (ref "U1") (pin "7") (pinfunction "NRST_7") (pintype "bidirectional"))
    )
    (net (code "55") (name "unconnected-(U1-PA0-WKUP-Pad14)") (class "Default")
      (node (ref "U1") (pin "14") (pinfunction "PA0-WKUP_14") (pintype "bidirectional"))
    )
    (net (code "56") (name "unconnected-(U1-PA4-Pad20)") (class "Default")
      (node (ref "U1") (pin "20") (pinfunction "PA4_20") (pintype "bidirectional"))
    )
    (net (code "57") (name "unconnected-(U1-PA5-Pad21)") (class "Default")
      (node (ref "U1") (pin "21") (pinfunction "PA5_21") (pintype "bidirectional"))
    )
    (net (code "58") (name "unconnected-(U1-PA6-Pad22)") (class "Default")
      (node (ref "U1") (pin "22") (pinfunction "PA6_22") (pintype "bidirectional"))
    )
    (net (code "59") (name "unconnected-(U1-PA7-Pad23)") (class "Default")
      (node (ref "U1") (pin "23") (pinfunction "PA7_23") (pintype "bidirectional"))
    )
    (net (code "60") (name "unconnected-(U1-PA8-Pad41)") (class "Default")
      (node (ref "U1") (pin "41") (pinfunction "PA8_41") (pintype "bidirectional"))
    )
    (net (code "61") (name "unconnected-(U1-PA9-Pad42)") (class "Default")
      (node (ref "U1") (pin "42") (pinfunction "PA9_42") (pintype "bidirectional"))
    )
    (net (code "62") (name "unconnected-(U1-PA10-Pad43)") (class "Default")
      (node (ref "U1") (pin "43") (pinfunction "PA10_43") (pintype "bidirectional"))
    )
    (net (code "63") (name "unconnected-(U1-PA11-Pad44)") (class "Default")
      (node (ref "U1") (pin "44") (pinfunction "PA11_44") (pintype "bidirectional"))
    )
    (net (code "64") (name "unconnected-(U1-PA12-Pad45)") (class "Default")
      (node (ref "U1") (pin "45") (pinfunction "PA12_45") (pintype "bidirectional"))
    )
    (net (code "65") (name "unconnected-(U1-PA15{slash}JTDI-Pad50)") (class "Default")
      (node (ref "U1") (pin "50") (pinfunction "PA15/JTDI_50") (pintype "bidirectional"))
    )
    (net (code "66") (name "unconnected-(U1-PB2{slash}BOOT1-Pad28)") (class "Default")
      (node (ref "U1") (pin "28") (pinfunction "PB2/BOOT1_28") (pintype "bidirectional"))
    )
    (net (code "67") (name "unconnected-(U1-PB3{slash}JTDO-Pad55)") (class "Default")
      (node (ref "U1") (pin "55") (pinfunction "PB3/JTDO_55") (pintype "bidirectional"))
    )
    (net (code "68") (name "unconnected-(U1-PB4{slash}JNTRST-Pad56)") (class "Default")
      (node (ref "U1") (pin "56") (pinfunction "PB4/JNTRST_56") (pintype "bidirectional"))
    )
    (net (code "69") (name "unconnected-(U1-PB5-Pad57)") (class "Default")
      (node (ref "U1") (pin "57") (pinfunction "PB5_57") (pintype "bidirectional"))
    )
    (net (code "70") (name "unconnected-(U1-PB7-Pad59)") (class "Default")
      (node (ref "U1") (pin "59") (pinfunction "PB7_59") (pintype "bidirectional"))
    )
    (net (code "71") (name "unconnected-(U1-PB8-Pad61)") (class "Default")
      (node (ref "U1") (pin "61") (pinfunction "PB8_61") (pintype "bidirectional"))
    )
    (net (code "72") (name "unconnected-(U1-PB9-Pad62)") (class "Default")
      (node (ref "U1") (pin "62") (pinfunction "PB9_62") (pintype "bidirectional"))
    )
    (net (code "73") (name "unconnected-(U1-PB14-Pad35)") (class "Default")
      (node (ref "U1") (pin "35") (pinfunction "PB14_35") (pintype "bidirectional"))
    )
    (net (code "74") (name "unconnected-(U1-PB15-Pad36)") (class "Default")
      (node (ref "U1") (pin "36") (pinfunction "PB15_36") (pintype "bidirectional"))
    )
    (net (code "75") (name "unconnected-(U1-PC0-Pad8)") (class "Default")
      (node (ref "U1") (pin "8") (pinfunction "PC0_8") (pintype "bidirectional"))
    )
    (net (code "76") (name "unconnected-(U1-PC1-Pad9)") (class "Default")
      (node (ref "U1") (pin "9") (pinfunction "PC1_9") (pintype "bidirectional"))
    )
    (net (code "77") (name "unconnected-(U1-PC2-Pad10)") (class "Default")
      (node (ref "U1") (pin "10") (pinfunction "PC2_10") (pintype "bidirectional"))
    )
    (net (code "78") (name "unconnected-(U1-PC3-Pad11)") (class "Default")
      (node (ref "U1") (pin "11") (pinfunction "PC3_11") (pintype "bidirectional"))
    )
    (net (code "79") (name "unconnected-(U1-PC4-Pad24)") (class "Default")
      (node (ref "U1") (pin "24") (pinfunction "PC4_24") (pintype "bidirectional"))
    )
    (net (code "80") (name "unconnected-(U1-PC5-Pad25)") (class "Default")
      (node (ref "U1") (pin "25") (pinfunction "PC5_25") (pintype "bidirectional"))
    )
    (net (code "81") (name "unconnected-(U1-PC6-Pad37)") (class "Default")
      (node (ref "U1") (pin "37") (pinfunction "PC6_37") (pintype "bidirectional"))
    )
    (net (code "82") (name "unconnected-(U1-PC7-Pad38)") (class "Default")
      (node (ref "U1") (pin "38") (pinfunction "PC7_38") (pintype "bidirectional"))
    )
    (net (code "83") (name "unconnected-(U1-PC8-Pad39)") (class "Default")
      (node (ref "U1") (pin "39") (pinfunction "PC8_39") (pintype "bidirectional"))
    )
    (net (code "84") (name "unconnected-(U1-PC9-Pad40)") (class "Default")
      (node (ref "U1") (pin "40") (pinfunction "PC9_40") (pintype "bidirectional"))
    )
    (net (code "85") (name "unconnected-(U1-PC10-Pad51)") (class "Default")
      (node (ref "U1") (pin "51") (pinfunction "PC10_51") (pintype "bidirectional"))
    )
    (net (code "86") (name "unconnected-(U1-PC11-Pad52)") (class "Default")
      (node (ref "U1") (pin "52") (pinfunction "PC11_52") (pintype "bidirectional"))
    )
    (net (code "87") (name "unconnected-(U1-PC12-Pad53)") (class "Default")
      (node (ref "U1") (pin "53") (pinfunction "PC12_53") (pintype "bidirectional"))
    )
    (net (code "88") (name "unconnected-(U1-PC15-OSC32_OUT-Pad4)") (class "Default")
      (node (ref "U1") (pin "4") (pinfunction "PC15-OSC32_OUT_4") (pintype "bidirectional"))
    )
    (net (code "89") (name "unconnected-(U1-PD2-Pad54)") (class "Default")
      (node (ref "U1") (pin "54") (pinfunction "PD2_54") (pintype "bidirectional"))
    )
    (net (code "90") (name "unconnected-(U1-VBAT-Pad1)") (class "Default")
      (node (ref "U1") (pin "1") (pinfunction "VBAT_1") (pintype "power_in"))
    )
    (net (code "91") (name "unconnected-(U4-EN-Pad2)") (class "Default")
      (node (ref "U4") (pin "2") (pinfunction "EN_2") (pintype "passive"))
    )
    (net (code "92") (name "unconnected-(U8-NC-Pad3)") (class "Default")
      (node (ref "U8") (pin "3") (pinfunction "NC_3") (pintype "passive"))
    )
    (net (code "93") (name "unconnected-(U8-NC-Pad4)") (class "Default")
      (node (ref "U8") (pin "4") (pinfunction "NC_4") (pintype "passive"))
    )
  )
)
